# Extra_Analogue_Inputs.net
KiCad netlist of a schematic drawn in Altium Designer
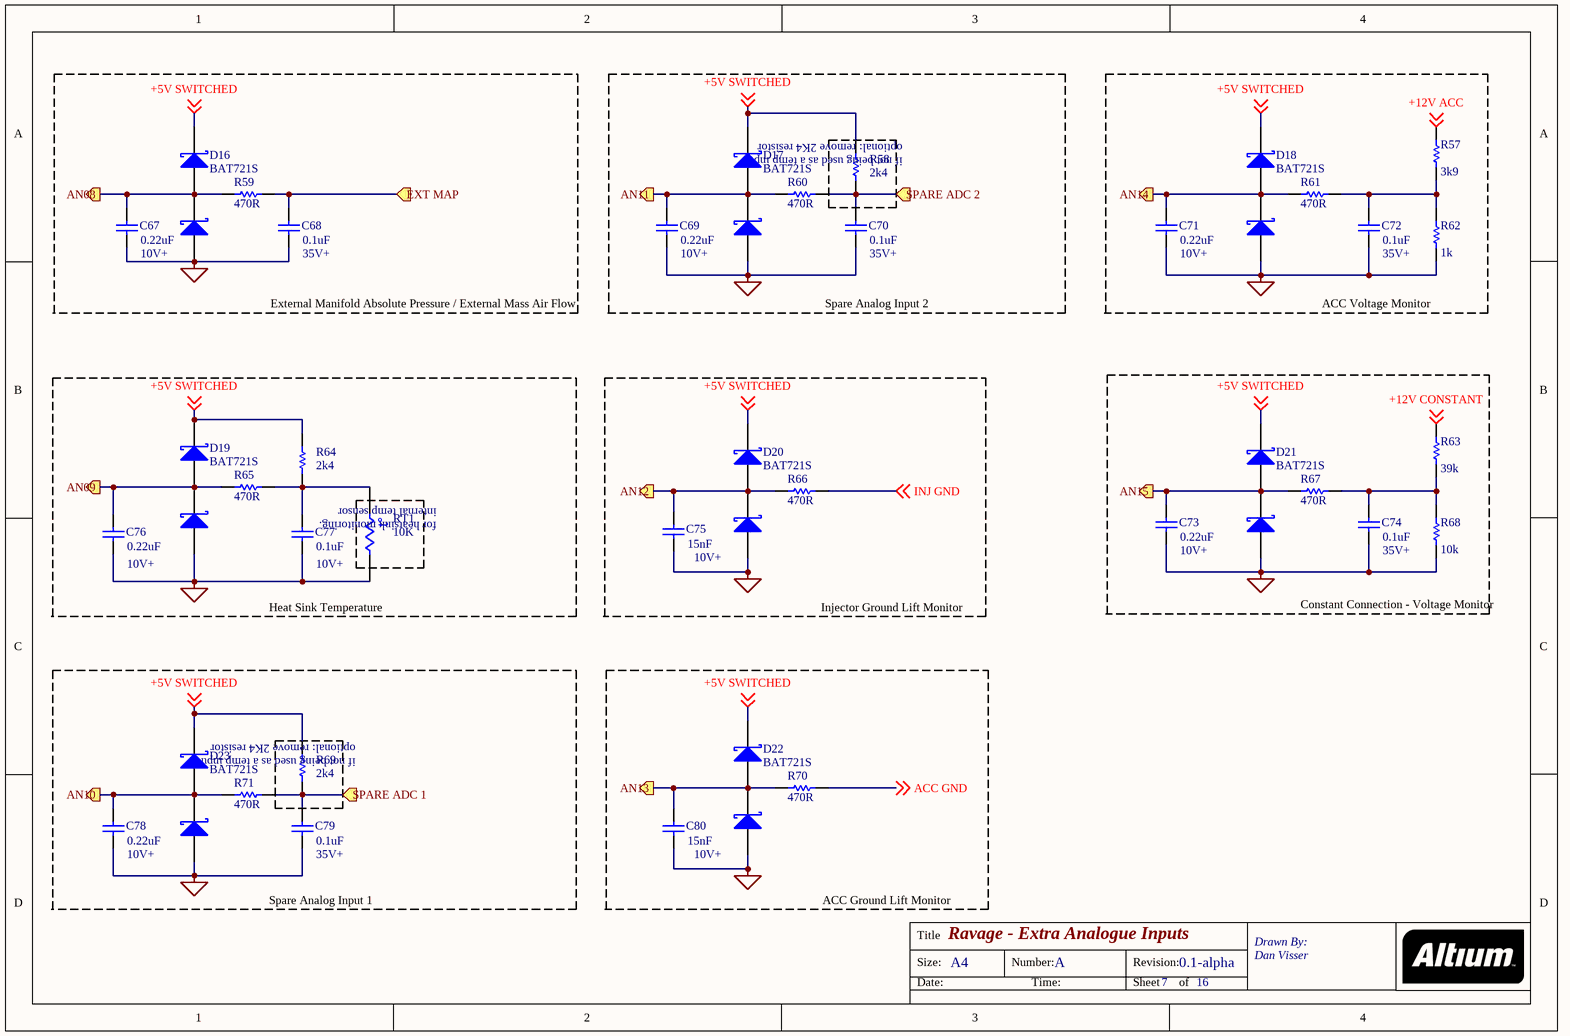
[diagram p0: Extra Analogue Inputs.SchDoc]

(export (version "E")
  (design (tool "Eeschema 10.0.6"))
  (components
    (comp (ref "C67")
      (value "0.22uF")
      (footprint "RAD-0.3")
      (description "Capacitor")
      (fields (field (name "PUBLISHER") "Altium Limited"))
      (libsource (lib "Miscellaneous Devices") (part "Cap"))
    )
    (comp (ref "C68")
      (value "0.1uF")
      (footprint "RAD-0.3")
      (description "Capacitor")
      (fields (field (name "PUBLISHER") "Altium Limited"))
      (libsource (lib "Miscellaneous Devices") (part "Cap"))
    )
    (comp (ref "C69")
      (value "0.22uF")
      (footprint "RAD-0.3")
      (description "Capacitor")
      (fields (field (name "PUBLISHER") "Altium Limited"))
      (libsource (lib "Miscellaneous Devices") (part "Cap"))
    )
    (comp (ref "C70")
      (value "0.1uF")
      (footprint "RAD-0.3")
      (description "Capacitor")
      (fields (field (name "PUBLISHER") "Altium Limited"))
      (libsource (lib "Miscellaneous Devices") (part "Cap"))
    )
    (comp (ref "C71")
      (value "0.22uF")
      (footprint "RAD-0.3")
      (description "Capacitor")
      (fields (field (name "PUBLISHER") "Altium Limited"))
      (libsource (lib "Miscellaneous Devices") (part "Cap"))
    )
    (comp (ref "C72")
      (value "0.1uF")
      (footprint "RAD-0.3")
      (description "Capacitor")
      (fields (field (name "PUBLISHER") "Altium Limited"))
      (libsource (lib "Miscellaneous Devices") (part "Cap"))
    )
    (comp (ref "C73")
      (value "0.22uF")
      (footprint "RAD-0.3")
      (description "Capacitor")
      (fields (field (name "PUBLISHER") "Altium Limited"))
      (libsource (lib "Miscellaneous Devices") (part "Cap"))
    )
    (comp (ref "C74")
      (value "0.1uF")
      (footprint "RAD-0.3")
      (description "Capacitor")
      (fields (field (name "PUBLISHER") "Altium Limited"))
      (libsource (lib "Miscellaneous Devices") (part "Cap"))
    )
    (comp (ref "C75")
      (value "15nF")
      (footprint "RAD-0.3")
      (description "Capacitor")
      (fields (field (name "PUBLISHER") "Altium Limited"))
      (libsource (lib "Miscellaneous Devices") (part "Cap"))
    )
    (comp (ref "C76")
      (value "0.22uF")
      (footprint "RAD-0.3")
      (description "Capacitor")
      (fields (field (name "PUBLISHER") "Altium Limited"))
      (libsource (lib "Miscellaneous Devices") (part "Cap"))
    )
    (comp (ref "C77")
      (value "0.1uF")
      (footprint "RAD-0.3")
      (description "Capacitor")
      (fields (field (name "PUBLISHER") "Altium Limited"))
      (libsource (lib "Miscellaneous Devices") (part "Cap"))
    )
    (comp (ref "C78")
      (value "0.22uF")
      (footprint "RAD-0.3")
      (description "Capacitor")
      (fields (field (name "PUBLISHER") "Altium Limited"))
      (libsource (lib "Miscellaneous Devices") (part "Cap"))
    )
    (comp (ref "C79")
      (value "0.1uF")
      (footprint "RAD-0.3")
      (description "Capacitor")
      (fields (field (name "PUBLISHER") "Altium Limited"))
      (libsource (lib "Miscellaneous Devices") (part "Cap"))
    )
    (comp (ref "C80")
      (value "15nF")
      (footprint "RAD-0.3")
      (description "Capacitor")
      (fields (field (name "PUBLISHER") "Altium Limited"))
      (libsource (lib "Miscellaneous Devices") (part "Cap"))
    )
    (comp (ref "D16")
      (value "BAT721S")
      (description "DUAL SCHOTTKY DIODE")
      (libsource (lib "FreeEMS Schematic Library") (part "BAT721S"))
    )
    (comp (ref "D17")
      (value "BAT721S")
      (description "DUAL SCHOTTKY DIODE")
      (libsource (lib "FreeEMS Schematic Library") (part "BAT721S"))
    )
    (comp (ref "D18")
      (value "BAT721S")
      (description "DUAL SCHOTTKY DIODE")
      (libsource (lib "FreeEMS Schematic Library") (part "BAT721S"))
    )
    (comp (ref "D19")
      (value "BAT721S")
      (description "DUAL SCHOTTKY DIODE")
      (libsource (lib "FreeEMS Schematic Library") (part "BAT721S"))
    )
    (comp (ref "D20")
      (value "BAT721S")
      (description "DUAL SCHOTTKY DIODE")
      (libsource (lib "FreeEMS Schematic Library") (part "BAT721S"))
    )
    (comp (ref "D21")
      (value "BAT721S")
      (description "DUAL SCHOTTKY DIODE")
      (libsource (lib "FreeEMS Schematic Library") (part "BAT721S"))
    )
    (comp (ref "D22")
      (value "BAT721S")
      (description "DUAL SCHOTTKY DIODE")
      (libsource (lib "FreeEMS Schematic Library") (part "BAT721S"))
    )
    (comp (ref "D23")
      (value "BAT721S")
      (description "DUAL SCHOTTKY DIODE")
      (libsource (lib "FreeEMS Schematic Library") (part "BAT721S"))
    )
    (comp (ref "R57")
      (value "3k9")
      (footprint "AXIAL-0.3")
      (description "Resistor")
      (fields (field (name "PUBLISHER") "Altium Limited"))
      (libsource (lib "Miscellaneous Devices") (part "Res1"))
    )
    (comp (ref "R58")
      (value "2k4")
      (footprint "AXIAL-0.3")
      (description "Resistor")
      (fields (field (name "PUBLISHER") "Altium Limited"))
      (libsource (lib "Miscellaneous Devices") (part "Res1"))
    )
    (comp (ref "R59")
      (value "470R")
      (footprint "AXIAL-0.3")
      (description "Resistor")
      (fields (field (name "PUBLISHER") "Altium Limited"))
      (libsource (lib "Miscellaneous Devices") (part "Res1"))
    )
    (comp (ref "R60")
      (value "470R")
      (footprint "AXIAL-0.3")
      (description "Resistor")
      (fields (field (name "PUBLISHER") "Altium Limited"))
      (libsource (lib "Miscellaneous Devices") (part "Res1"))
    )
    (comp (ref "R61")
      (value "470R")
      (footprint "AXIAL-0.3")
      (description "Resistor")
      (fields (field (name "PUBLISHER") "Altium Limited"))
      (libsource (lib "Miscellaneous Devices") (part "Res1"))
    )
    (comp (ref "R62")
      (value "1k")
      (footprint "AXIAL-0.3")
      (description "Resistor")
      (fields (field (name "PUBLISHER") "Altium Limited"))
      (libsource (lib "Miscellaneous Devices") (part "Res1"))
    )
    (comp (ref "R63")
      (value "39k")
      (footprint "AXIAL-0.3")
      (description "Resistor")
      (fields (field (name "PUBLISHER") "Altium Limited"))
      (libsource (lib "Miscellaneous Devices") (part "Res1"))
    )
    (comp (ref "R64")
      (value "2k4")
      (footprint "AXIAL-0.3")
      (description "Resistor")
      (fields (field (name "PUBLISHER") "Altium Limited"))
      (libsource (lib "Miscellaneous Devices") (part "Res1"))
    )
    (comp (ref "R65")
      (value "470R")
      (footprint "AXIAL-0.3")
      (description "Resistor")
      (fields (field (name "PUBLISHER") "Altium Limited"))
      (libsource (lib "Miscellaneous Devices") (part "Res1"))
    )
    (comp (ref "R66")
      (value "470R")
      (footprint "AXIAL-0.3")
      (description "Resistor")
      (fields (field (name "PUBLISHER") "Altium Limited"))
      (libsource (lib "Miscellaneous Devices") (part "Res1"))
    )
    (comp (ref "R67")
      (value "470R")
      (footprint "AXIAL-0.3")
      (description "Resistor")
      (fields (field (name "PUBLISHER") "Altium Limited"))
      (libsource (lib "Miscellaneous Devices") (part "Res1"))
    )
    (comp (ref "R68")
      (value "10k")
      (footprint "AXIAL-0.3")
      (description "Resistor")
      (fields (field (name "PUBLISHER") "Altium Limited"))
      (libsource (lib "Miscellaneous Devices") (part "Res1"))
    )
    (comp (ref "R69")
      (value "2k4")
      (footprint "AXIAL-0.3")
      (description "Resistor")
      (fields (field (name "PUBLISHER") "Altium Limited"))
      (libsource (lib "Miscellaneous Devices") (part "Res1"))
    )
    (comp (ref "R70")
      (value "470R")
      (footprint "AXIAL-0.3")
      (description "Resistor")
      (fields (field (name "PUBLISHER") "Altium Limited"))
      (libsource (lib "Miscellaneous Devices") (part "Res1"))
    )
    (comp (ref "R71")
      (value "470R")
      (footprint "AXIAL-0.3")
      (description "Resistor")
      (fields (field (name "PUBLISHER") "Altium Limited"))
      (libsource (lib "Miscellaneous Devices") (part "Res1"))
    )
    (comp (ref "RT1")
      (value "10K")
      (footprint "6-0805_N")
      (description "Thermistor")
      (fields (field (name "PUBLISHER") "Altium Limited"))
      (libsource (lib "Miscellaneous Devices") (part "Res Thermal"))
    )
  )
  (nets
    (net (code "1") (name "+5V SWITCHED") (class "Default")
      (node (ref "D16") (pin "2") (pinfunction "K_2") (pintype "passive"))
      (node (ref "D17") (pin "2") (pinfunction "K_2") (pintype "passive"))
      (node (ref "D18") (pin "2") (pinfunction "K_2") (pintype "passive"))
      (node (ref "D19") (pin "2") (pinfunction "K_2") (pintype "passive"))
      (node (ref "D20") (pin "2") (pinfunction "K_2") (pintype "passive"))
      (node (ref "D21") (pin "2") (pinfunction "K_2") (pintype "passive"))
      (node (ref "D22") (pin "2") (pinfunction "K_2") (pintype "passive"))
      (node (ref "D23") (pin "2") (pinfunction "K_2") (pintype "passive"))
      (node (ref "R58") (pin "1") (pinfunction "1_1") (pintype "passive"))
      (node (ref "R64") (pin "1") (pinfunction "1_1") (pintype "passive"))
      (node (ref "R69") (pin "1") (pinfunction "1_1") (pintype "passive"))
    )
    (net (code "2") (name "+12V ACC") (class "Default")
      (node (ref "R57") (pin "2") (pinfunction "2_2") (pintype "passive"))
    )
    (net (code "3") (name "+12V CONSTANT") (class "Default")
      (node (ref "R63") (pin "2") (pinfunction "2_2") (pintype "passive"))
    )
    (net (code "4") (name "/AN08") (class "Default")
      (node (ref "C67") (pin "2") (pinfunction "2_2") (pintype "passive"))
      (node (ref "D16") (pin "3") (pinfunction "A2_3") (pintype "passive"))
      (node (ref "R59") (pin "1") (pinfunction "1_1") (pintype "passive"))
    )
    (net (code "5") (name "/AN09") (class "Default")
      (node (ref "C76") (pin "2") (pinfunction "2_2") (pintype "passive"))
      (node (ref "D19") (pin "3") (pinfunction "A2_3") (pintype "passive"))
      (node (ref "R65") (pin "1") (pinfunction "1_1") (pintype "passive"))
    )
    (net (code "6") (name "/AN10") (class "Default")
      (node (ref "C78") (pin "2") (pinfunction "2_2") (pintype "passive"))
      (node (ref "D23") (pin "3") (pinfunction "A2_3") (pintype "passive"))
      (node (ref "R71") (pin "1") (pinfunction "1_1") (pintype "passive"))
    )
    (net (code "7") (name "/AN11") (class "Default")
      (node (ref "C69") (pin "2") (pinfunction "2_2") (pintype "passive"))
      (node (ref "D17") (pin "3") (pinfunction "A2_3") (pintype "passive"))
      (node (ref "R60") (pin "1") (pinfunction "1_1") (pintype "passive"))
    )
    (net (code "8") (name "/AN12") (class "Default")
      (node (ref "C75") (pin "2") (pinfunction "2_2") (pintype "passive"))
      (node (ref "D20") (pin "3") (pinfunction "A2_3") (pintype "passive"))
      (node (ref "R66") (pin "1") (pinfunction "1_1") (pintype "passive"))
    )
    (net (code "9") (name "/AN13") (class "Default")
      (node (ref "C80") (pin "2") (pinfunction "2_2") (pintype "passive"))
      (node (ref "D22") (pin "3") (pinfunction "A2_3") (pintype "passive"))
      (node (ref "R70") (pin "1") (pinfunction "1_1") (pintype "passive"))
    )
    (net (code "10") (name "/AN14") (class "Default")
      (node (ref "C71") (pin "2") (pinfunction "2_2") (pintype "passive"))
      (node (ref "D18") (pin "3") (pinfunction "A2_3") (pintype "passive"))
      (node (ref "R61") (pin "1") (pinfunction "1_1") (pintype "passive"))
    )
    (net (code "11") (name "/AN15") (class "Default")
      (node (ref "C73") (pin "2") (pinfunction "2_2") (pintype "passive"))
      (node (ref "D21") (pin "3") (pinfunction "A2_3") (pintype "passive"))
      (node (ref "R67") (pin "1") (pinfunction "1_1") (pintype "passive"))
    )
    (net (code "12") (name "/EXT MAP") (class "Default")
      (node (ref "C68") (pin "2") (pinfunction "2_2") (pintype "passive"))
      (node (ref "R59") (pin "2") (pinfunction "2_2") (pintype "passive"))
    )
    (net (code "13") (name "/SPARE ADC 1") (class "Default")
      (node (ref "C79") (pin "2") (pinfunction "2_2") (pintype "passive"))
      (node (ref "R69") (pin "2") (pinfunction "2_2") (pintype "passive"))
      (node (ref "R71") (pin "2") (pinfunction "2_2") (pintype "passive"))
    )
    (net (code "14") (name "/SPARE ADC 2") (class "Default")
      (node (ref "C70") (pin "2") (pinfunction "2_2") (pintype "passive"))
      (node (ref "R58") (pin "2") (pinfunction "2_2") (pintype "passive"))
      (node (ref "R60") (pin "2") (pinfunction "2_2") (pintype "passive"))
    )
    (net (code "15") (name "<NO NET>") (class "Default")
      (node (ref "C67") (pin "1") (pinfunction "1_1") (pintype "passive"))
      (node (ref "C68") (pin "1") (pinfunction "1_1") (pintype "passive"))
      (node (ref "C69") (pin "1") (pinfunction "1_1") (pintype "passive"))
      (node (ref "C70") (pin "1") (pinfunction "1_1") (pintype "passive"))
      (node (ref "C71") (pin "1") (pinfunction "1_1") (pintype "passive"))
      (node (ref "C72") (pin "1") (pinfunction "1_1") (pintype "passive"))
      (node (ref "C73") (pin "1") (pinfunction "1_1") (pintype "passive"))
      (node (ref "C74") (pin "1") (pinfunction "1_1") (pintype "passive"))
      (node (ref "C75") (pin "1") (pinfunction "1_1") (pintype "passive"))
      (node (ref "C76") (pin "1") (pinfunction "1_1") (pintype "passive"))
      (node (ref "C77") (pin "1") (pinfunction "1_1") (pintype "passive"))
      (node (ref "C78") (pin "1") (pinfunction "1_1") (pintype "passive"))
      (node (ref "C79") (pin "1") (pinfunction "1_1") (pintype "passive"))
      (node (ref "C80") (pin "1") (pinfunction "1_1") (pintype "passive"))
      (node (ref "D16") (pin "1") (pinfunction "A_1") (pintype "passive"))
      (node (ref "D17") (pin "1") (pinfunction "A_1") (pintype "passive"))
      (node (ref "D18") (pin "1") (pinfunction "A_1") (pintype "passive"))
      (node (ref "D19") (pin "1") (pinfunction "A_1") (pintype "passive"))
      (node (ref "D20") (pin "1") (pinfunction "A_1") (pintype "passive"))
      (node (ref "D21") (pin "1") (pinfunction "A_1") (pintype "passive"))
      (node (ref "D22") (pin "1") (pinfunction "A_1") (pintype "passive"))
      (node (ref "D23") (pin "1") (pinfunction "A_1") (pintype "passive"))
      (node (ref "R62") (pin "1") (pinfunction "1_1") (pintype "passive"))
      (node (ref "R68") (pin "1") (pinfunction "1_1") (pintype "passive"))
      (node (ref "RT1") (pin "2") (pinfunction "2_2") (pintype "passive"))
    )
    (net (code "16") (name "ACC GND") (class "Default")
      (node (ref "R70") (pin "2") (pinfunction "2_2") (pintype "passive"))
    )
    (net (code "17") (name "INJ GND") (class "Default")
      (node (ref "R66") (pin "2") (pinfunction "2_2") (pintype "passive"))
    )
    (net (code "18") (name "Net-(C72-Pad2)") (class "Default")
      (node (ref "C72") (pin "2") (pinfunction "2_2") (pintype "passive"))
      (node (ref "R57") (pin "1") (pinfunction "1_1") (pintype "passive"))
      (node (ref "R61") (pin "2") (pinfunction "2_2") (pintype "passive"))
      (node (ref "R62") (pin "2") (pinfunction "2_2") (pintype "passive"))
    )
    (net (code "19") (name "Net-(C74-Pad2)") (class "Default")
      (node (ref "C74") (pin "2") (pinfunction "2_2") (pintype "passive"))
      (node (ref "R63") (pin "1") (pinfunction "1_1") (pintype "passive"))
      (node (ref "R67") (pin "2") (pinfunction "2_2") (pintype "passive"))
      (node (ref "R68") (pin "2") (pinfunction "2_2") (pintype "passive"))
    )
    (net (code "20") (name "Net-(C77-Pad2)") (class "Default")
      (node (ref "C77") (pin "2") (pinfunction "2_2") (pintype "passive"))
      (node (ref "R64") (pin "2") (pinfunction "2_2") (pintype "passive"))
      (node (ref "R65") (pin "2") (pinfunction "2_2") (pintype "passive"))
      (node (ref "RT1") (pin "1") (pinfunction "1_1") (pintype "passive"))
    )
  )
)
